# SourceFollower_SOT343_Modular.net
KiCad netlist of a schematic drawn in Altium Designer
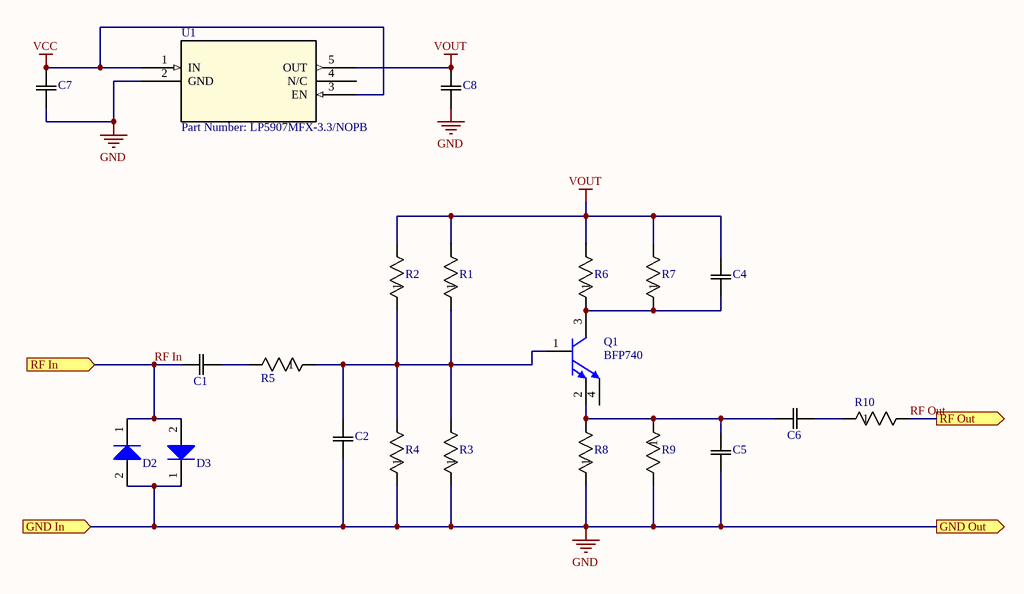
[diagram p0: SourceFollower_SOT343_Modular.SchDoc]

(export (version "E")
  (design (tool "Eeschema 10.0.6"))
  (components
    (comp (ref "C1")
      (value "Part Number: C0201C270J3GACTU")
      (footprint "C0201")
      (description "No Description Available")
      (fields
        (field (name "MANUFACTURER_PART_NUMBER") "C0201C270J3GACTU")
        (field (name "COPYRIGHT") "Copyright (C) 2018 Accelerated Designs. All rights reserved")
      )
      (libsource (lib "0201Capacitor_Yageo") (part "C0201C270J3GACTU"))
    )
    (comp (ref "C2")
      (value "Part Number: C0201C270J3GACTU")
      (footprint "C0201")
      (description "No Description Available")
      (fields
        (field (name "MANUFACTURER_PART_NUMBER") "C0201C270J3GACTU")
        (field (name "COPYRIGHT") "Copyright (C) 2018 Accelerated Designs. All rights reserved")
      )
      (libsource (lib "0201Capacitor_Yageo") (part "C0201C270J3GACTU"))
    )
    (comp (ref "C4")
      (value "Part Number: C0201C270J3GACTU")
      (footprint "C0201")
      (description "No Description Available")
      (fields
        (field (name "MANUFACTURER_PART_NUMBER") "C0201C270J3GACTU")
        (field (name "COPYRIGHT") "Copyright (C) 2018 Accelerated Designs. All rights reserved")
      )
      (libsource (lib "0201Capacitor_Yageo") (part "C0201C270J3GACTU"))
    )
    (comp (ref "C5")
      (value "Part Number: C0201C270J3GACTU")
      (footprint "C0201")
      (description "No Description Available")
      (fields
        (field (name "MANUFACTURER_PART_NUMBER") "C0201C270J3GACTU")
        (field (name "COPYRIGHT") "Copyright (C) 2018 Accelerated Designs. All rights reserved")
      )
      (libsource (lib "0201Capacitor_Yageo") (part "C0201C270J3GACTU"))
    )
    (comp (ref "C6")
      (value "Part Number: C0201C270J3GACTU")
      (footprint "C0201")
      (description "No Description Available")
      (fields
        (field (name "MANUFACTURER_PART_NUMBER") "C0201C270J3GACTU")
        (field (name "COPYRIGHT") "Copyright (C) 2018 Accelerated Designs. All rights reserved")
      )
      (libsource (lib "0201Capacitor_Yageo") (part "C0201C270J3GACTU"))
    )
    (comp (ref "C7")
      (value "Part Number: CC0402KRX7R6BB104")
      (footprint "YAG_CC0402")
      (description "No Description Available")
      (fields
        (field (name "MANUFACTURER_PART_NUMBER") "CC0402KRX7R6BB104")
        (field (name "COPYRIGHT") "Copyright (C) 2018 Accelerated Designs. All rights reserved")
      )
      (libsource (lib "0402Capacitor_Yageo") (part "CC0402KRX7R6BB10"))
    )
    (comp (ref "C8")
      (value "Part Number: CC0402KRX7R6BB104")
      (footprint "YAG_CC0402")
      (description "No Description Available")
      (fields
        (field (name "MANUFACTURER_PART_NUMBER") "CC0402KRX7R6BB104")
        (field (name "COPYRIGHT") "Copyright (C) 2018 Accelerated Designs. All rights reserved")
      )
      (libsource (lib "0402Capacitor_Yageo") (part "CC0402KRX7R6BB10"))
    )
    (comp (ref "D2")
      (value "BAT15-03W")
      (footprint "INF-SOD323_V")
      (description "Single Silicon Schottky Diode, 110 mA IF Max, SOD32, Green")
      (fields (field (name "MANUFACTURER") "Infineon"))
      (libsource (lib "Infineon_RFSchottkyDiode_SOD323") (part "BAT15-03W"))
    )
    (comp (ref "D3")
      (value "BAT15-03W")
      (footprint "INF-SOD323_V")
      (description "Single Silicon Schottky Diode, 110 mA IF Max, SOD32, Green")
      (fields (field (name "MANUFACTURER") "Infineon"))
      (libsource (lib "Infineon_RFSchottkyDiode_SOD323") (part "BAT15-03W"))
    )
    (comp (ref "Q1")
      (value "BFP740")
      (footprint "INF-SOT343_V")
      (description "NPN Silicon Germanium RF Transistor, 4 V VCEO, 45 mA IC, 27 dB Gmax, SOT343, Green")
      (fields (field (name "MANUFACTURER") "Infineon"))
      (libsource (lib "Infineon_RFBJT_SOT343") (part "BFP740"))
    )
    (comp (ref "R1")
      (value "Part Number: RC0201FR-0718KL")
      (footprint "RES_RC0201_P6XP3")
      (description "No Description Available")
      (fields
        (field (name "MANUFACTURER_PART_NUMBER") "RC0201FR-0718KL")
        (field (name "COPYRIGHT") "Copyright (C) 2018 Accelerated Designs. All rights reserved")
      )
      (libsource (lib "0201Resistor_Yageo") (part "RC0201FR-0718KL"))
    )
    (comp (ref "R2")
      (value "Part Number: RC0201FR-0718KL")
      (footprint "RES_RC0201_P6XP3")
      (description "No Description Available")
      (fields
        (field (name "MANUFACTURER_PART_NUMBER") "RC0201FR-0718KL")
        (field (name "COPYRIGHT") "Copyright (C) 2018 Accelerated Designs. All rights reserved")
      )
      (libsource (lib "0201Resistor_Yageo") (part "RC0201FR-0718KL"))
    )
    (comp (ref "R3")
      (value "Part Number: RC0201FR-0718KL")
      (footprint "RES_RC0201_P6XP3")
      (description "No Description Available")
      (fields
        (field (name "MANUFACTURER_PART_NUMBER") "RC0201FR-0718KL")
        (field (name "COPYRIGHT") "Copyright (C) 2018 Accelerated Designs. All rights reserved")
      )
      (libsource (lib "0201Resistor_Yageo") (part "RC0201FR-0718KL"))
    )
    (comp (ref "R4")
      (value "Part Number: RC0201FR-0718KL")
      (footprint "RES_RC0201_P6XP3")
      (description "No Description Available")
      (fields
        (field (name "MANUFACTURER_PART_NUMBER") "RC0201FR-0718KL")
        (field (name "COPYRIGHT") "Copyright (C) 2018 Accelerated Designs. All rights reserved")
      )
      (libsource (lib "0201Resistor_Yageo") (part "RC0201FR-0718KL"))
    )
    (comp (ref "R5")
      (value "Part Number: RC0201FR-0718KL")
      (footprint "RES_RC0201_P6XP3")
      (description "No Description Available")
      (fields
        (field (name "MANUFACTURER_PART_NUMBER") "RC0201FR-0718KL")
        (field (name "COPYRIGHT") "Copyright (C) 2018 Accelerated Designs. All rights reserved")
      )
      (libsource (lib "0201Resistor_Yageo") (part "RC0201FR-0718KL"))
    )
    (comp (ref "R6")
      (value "Part Number: RC0201FR-0718KL")
      (footprint "RES_RC0201_P6XP3")
      (description "No Description Available")
      (fields
        (field (name "MANUFACTURER_PART_NUMBER") "RC0201FR-0718KL")
        (field (name "COPYRIGHT") "Copyright (C) 2018 Accelerated Designs. All rights reserved")
      )
      (libsource (lib "0201Resistor_Yageo") (part "RC0201FR-0718KL"))
    )
    (comp (ref "R7")
      (value "Part Number: RC0201FR-0718KL")
      (footprint "RES_RC0201_P6XP3")
      (description "No Description Available")
      (fields
        (field (name "MANUFACTURER_PART_NUMBER") "RC0201FR-0718KL")
        (field (name "COPYRIGHT") "Copyright (C) 2018 Accelerated Designs. All rights reserved")
      )
      (libsource (lib "0201Resistor_Yageo") (part "RC0201FR-0718KL"))
    )
    (comp (ref "R8")
      (value "Part Number: RC0201FR-0718KL")
      (footprint "RES_RC0201_P6XP3")
      (description "No Description Available")
      (fields
        (field (name "MANUFACTURER_PART_NUMBER") "RC0201FR-0718KL")
        (field (name "COPYRIGHT") "Copyright (C) 2018 Accelerated Designs. All rights reserved")
      )
      (libsource (lib "0201Resistor_Yageo") (part "RC0201FR-0718KL"))
    )
    (comp (ref "R9")
      (value "Part Number: RC0201FR-0718KL")
      (footprint "RES_RC0201_P6XP3")
      (description "No Description Available")
      (fields
        (field (name "MANUFACTURER_PART_NUMBER") "RC0201FR-0718KL")
        (field (name "COPYRIGHT") "Copyright (C) 2018 Accelerated Designs. All rights reserved")
      )
      (libsource (lib "0201Resistor_Yageo") (part "RC0201FR-0718KL"))
    )
    (comp (ref "R10")
      (value "Part Number: RC0201FR-0718KL")
      (footprint "RES_RC0201_P6XP3")
      (description "No Description Available")
      (fields
        (field (name "MANUFACTURER_PART_NUMBER") "RC0201FR-0718KL")
        (field (name "COPYRIGHT") "Copyright (C) 2018 Accelerated Designs. All rights reserved")
      )
      (libsource (lib "0201Resistor_Yageo") (part "RC0201FR-0718KL"))
    )
    (comp (ref "U1")
      (value "Part Number: LP5907MFX-3.3/NOPB")
      (footprint "DBV5")
      (description "No Description Available")
      (fields
        (field (name "MANUFACTURER_PART_NUMBER") "LP5907MFX-3.3/NOPB")
        (field (name "COPYRIGHT") "Copyright (C) 2018 Accelerated Designs. All rights reserved")
      )
      (libsource (lib "TI_LDO_3V3_SOT325") (part "LP5907MFX-3.3/NO"))
    )
  )
  (nets
    (net (code "1") (name "/RF In") (class "Default")
      (node (ref "C1") (pin "1") (pinfunction "1_1") (pintype "passive"))
      (node (ref "D2") (pin "1") (pinfunction "K_1") (pintype "passive"))
      (node (ref "D3") (pin "2") (pinfunction "A_2") (pintype "passive"))
    )
    (net (code "2") (name "/RF Out") (class "Default")
      (node (ref "R10") (pin "2") (pinfunction "2_2") (pintype "passive"))
    )
    (net (code "3") (name "GND") (class "Default")
      (node (ref "C2") (pin "1") (pinfunction "1_1") (pintype "passive"))
      (node (ref "C5") (pin "1") (pinfunction "1_1") (pintype "passive"))
      (node (ref "C7") (pin "1") (pinfunction "1_1") (pintype "passive"))
      (node (ref "C8") (pin "1") (pinfunction "1_1") (pintype "passive"))
      (node (ref "D2") (pin "2") (pinfunction "A_2") (pintype "passive"))
      (node (ref "D3") (pin "1") (pinfunction "K_1") (pintype "passive"))
      (node (ref "R3") (pin "1") (pinfunction "1_1") (pintype "passive"))
      (node (ref "R4") (pin "1") (pinfunction "1_1") (pintype "passive"))
      (node (ref "R8") (pin "1") (pinfunction "1_1") (pintype "passive"))
      (node (ref "R9") (pin "2") (pinfunction "2_2") (pintype "passive"))
      (node (ref "U1") (pin "2") (pinfunction "GND_2") (pintype "power_in"))
    )
    (net (code "4") (name "Net-(C1-Pad2)") (class "Default")
      (node (ref "C1") (pin "2") (pinfunction "2_2") (pintype "passive"))
      (node (ref "R5") (pin "2") (pinfunction "2_2") (pintype "passive"))
    )
    (net (code "5") (name "Net-(C5-Pad2)") (class "Default")
      (node (ref "C5") (pin "2") (pinfunction "2_2") (pintype "passive"))
      (node (ref "C6") (pin "2") (pinfunction "2_2") (pintype "passive"))
      (node (ref "Q1") (pin "2") (pinfunction "E_2") (pintype "passive"))
      (node (ref "R8") (pin "2") (pinfunction "2_2") (pintype "passive"))
      (node (ref "R9") (pin "1") (pinfunction "1_1") (pintype "passive"))
    )
    (net (code "6") (name "Net-(C6-Pad1)") (class "Default")
      (node (ref "C6") (pin "1") (pinfunction "1_1") (pintype "passive"))
      (node (ref "R10") (pin "1") (pinfunction "1_1") (pintype "passive"))
    )
    (net (code "7") (name "Net-(Q1-B)") (class "Default")
      (node (ref "C2") (pin "2") (pinfunction "2_2") (pintype "passive"))
      (node (ref "Q1") (pin "1") (pinfunction "B_1") (pintype "passive"))
      (node (ref "R1") (pin "1") (pinfunction "1_1") (pintype "passive"))
      (node (ref "R2") (pin "1") (pinfunction "1_1") (pintype "passive"))
      (node (ref "R3") (pin "2") (pinfunction "2_2") (pintype "passive"))
      (node (ref "R4") (pin "2") (pinfunction "2_2") (pintype "passive"))
      (node (ref "R5") (pin "1") (pinfunction "1_1") (pintype "passive"))
    )
    (net (code "8") (name "Net-(Q1-C)") (class "Default")
      (node (ref "C4") (pin "1") (pinfunction "1_1") (pintype "passive"))
      (node (ref "Q1") (pin "3") (pinfunction "C_3") (pintype "passive"))
      (node (ref "R6") (pin "1") (pinfunction "1_1") (pintype "passive"))
      (node (ref "R7") (pin "1") (pinfunction "1_1") (pintype "passive"))
    )
    (net (code "9") (name "VCC") (class "Default")
      (node (ref "C7") (pin "2") (pinfunction "2_2") (pintype "passive"))
      (node (ref "U1") (pin "1") (pinfunction "IN_1") (pintype "input"))
      (node (ref "U1") (pin "3") (pinfunction "EN_3") (pintype "input"))
    )
    (net (code "10") (name "VOUT") (class "Default")
      (node (ref "C4") (pin "2") (pinfunction "2_2") (pintype "passive"))
      (node (ref "C8") (pin "2") (pinfunction "2_2") (pintype "passive"))
      (node (ref "R1") (pin "2") (pinfunction "2_2") (pintype "passive"))
      (node (ref "R2") (pin "2") (pinfunction "2_2") (pintype "passive"))
      (node (ref "R6") (pin "2") (pinfunction "2_2") (pintype "passive"))
      (node (ref "R7") (pin "2") (pinfunction "2_2") (pintype "passive"))
      (node (ref "U1") (pin "5") (pinfunction "OUT_5") (pintype "output"))
    )
    (net (code "11") (name "unconnected-(Q1-E-Pad4)") (class "Default")
      (node (ref "Q1") (pin "4") (pinfunction "E_4") (pintype "passive"))
    )
    (net (code "12") (name "unconnected-(U1-N{slash}C-Pad4)") (class "Default")
      (node (ref "U1") (pin "4") (pinfunction "N/C_4") (pintype "passive"))
    )
  )
)
